# TPS630250RNCT_Buck-Boost_Switching_Regul.net
KiCad netlist of a schematic drawn in Altium Designer
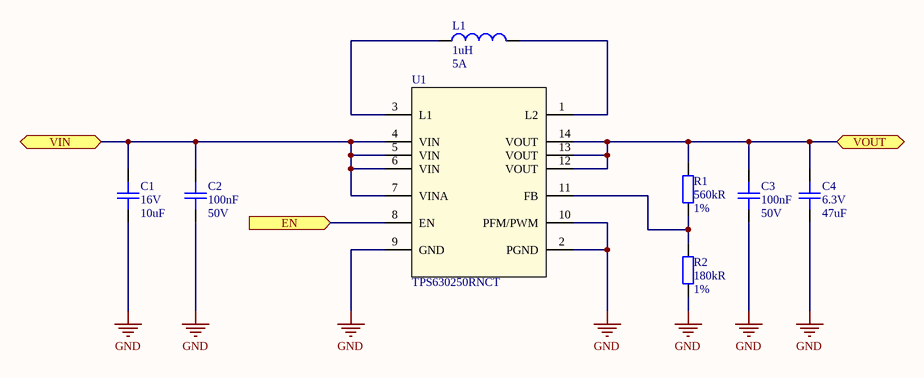
[diagram p0: TPS630250RNCT Buck-Boost Switching Regulator.SchDoc]

(export (version "E")
  (design (tool "Eeschema 10.0.6"))
  (components
    (comp (ref "C1")
      (value "CAP CER 10UF 16V X5R 0603")
      (footprint "C0603")
      (description "10µF ±10% 16V Ceramic Capacitor X5R 0603 (1608 Metric)")
      (fields
        (field (name "MANUFACTURER") "Murata")
        (field (name "MANUFACTURER PART NUMBER") "GRM188R61C106KAALJ")
        (field (name "VOLTAGE RATING") "16V")
        (field (name "CAPACITANCE") "10uF")
      )
      (libsource (lib "Control_Board_Model") (part "CAP CER 10UF 16V X5R 0603"))
    )
    (comp (ref "C2")
      (value "CAP CER 0.1UF 50V X7R 0402")
      (footprint "C0402")
      (description "0.1µF ±10% 50V Ceramic Capacitor X7R 0402 (1005 Metric)")
      (fields
        (field (name "MANUFACTURER") "TDK")
        (field (name "MANUFACTURER PART NUMBER") "CGA2B3X7R1H104K050BB")
        (field (name "CAPACITANCE") "100nF")
        (field (name "VOLTAGE") "50V")
      )
      (libsource (lib "Control_Board_Model") (part "CAP CER 0.1UF 50V X7R 0402"))
    )
    (comp (ref "C3")
      (value "CAP CER 0.1UF 50V X7R 0402")
      (footprint "C0402")
      (description "0.1µF ±10% 50V Ceramic Capacitor X7R 0402 (1005 Metric)")
      (fields
        (field (name "MANUFACTURER") "TDK")
        (field (name "MANUFACTURER PART NUMBER") "CGA2B3X7R1H104K050BB")
        (field (name "CAPACITANCE") "100nF")
        (field (name "VOLTAGE") "50V")
      )
      (libsource (lib "Control_Board_Model") (part "CAP CER 0.1UF 50V X7R 0402"))
    )
    (comp (ref "C4")
      (value "CAP CER 47UF 6.3V X5R 0603")
      (footprint "C0603")
      (description "47 µF ±20% 6.3V Ceramic Capacitor X5R 0603 (1608 Metric)")
      (fields
        (field (name "MANUFACTURER") "AVX Corporation")
        (field (name "MANUFACTURER PART NUMBER") "06036D476MAT2A")
        (field (name "VOLTAGE RATING") "6.3V")
        (field (name "CAPACITANCE") "47uF")
      )
      (libsource (lib "Control_Board_Model") (part "CAP CER 47UF 6.3V X5R 0603"))
    )
    (comp (ref "L1")
      (value "FIXED IND 1UH 5A 24 MOHM SMD")
      (footprint "IND_IHLP-1212B00")
      (description "1µH Shielded Molded Inductor 5A 24mOhm Max Nonstandard")
      (fields
        (field (name "MANUFACTURER") "Vishay Dale")
        (field (name "MANUFACTURER PART NUMBER") "IHLP1212BZER1R0M11")
        (field (name "INDUCTANCE") "1uH")
        (field (name "CURRENT RATING") "5A")
      )
      (libsource (lib "Control_Board_Model") (part "FIXED IND 1UH 5A 24 MOHM SMD"))
    )
    (comp (ref "R1")
      (value "RES SMD 560K OHM 1% 1/16W 0402")
      (footprint "R0402")
      (description "560 kOhms ±1% 0.063W, 1/16W Chip Resistor 0402 (1005 Metric) Moisture Resistant Thick Film")
      (fields
        (field (name "MANUFACTURER") "Yageo")
        (field (name "MANUFACTURER PART NUMBER") "RC0402FR-07560KL")
        (field (name "RESISTANCE") "560kR")
        (field (name "TOLERANCE") "1%")
      )
      (libsource (lib "Control_Board_Model") (part "RES SMD 560K OHM 1% 1/16W 0402"))
    )
    (comp (ref "R2")
      (value "RES SMD 180K OHM 1% 1/16W 0402")
      (footprint "R0402")
      (description "180 kOhms ±1% 0.063W, 1/16W Chip Resistor 0402 (1005 Metric) Moisture Resistant Thick Film")
      (fields
        (field (name "MANUFACTURER") "Yageo")
        (field (name "MANUFACTURER PART NUMBER") "RC0402FR-07180KL")
        (field (name "RESISTANCE") "180kR")
        (field (name "TOLERANCE") "1%")
      )
      (libsource (lib "Control_Board_Model") (part "RES SMD 180K OHM 1% 1/16W 0402"))
    )
    (comp (ref "U1")
      (value "TPS630250RNCT")
      (footprint "VFQFN-14")
      (description "Buck-Boost Switching Regulator IC Positive Adjustable 2.3V 1 Output 2A, 4A 14-VFQFN")
      (fields (field (name "MANUFACTURER") "Texas Instruments"))
      (libsource (lib "Control_Board_Model") (part "IC TPS630250RNCT REG BCK BST ADJ 2A/4A 14VQFN"))
    )
  )
  (nets
    (net (code "1") (name "/EN") (class "Default")
      (node (ref "U1") (pin "8") (pinfunction "EN_8") (pintype "passive"))
    )
    (net (code "2") (name "/VIN") (class "Default")
      (node (ref "C1") (pin "2") (pinfunction "2_2") (pintype "passive"))
      (node (ref "C2") (pin "2") (pinfunction "2_2") (pintype "passive"))
      (node (ref "U1") (pin "4") (pinfunction "VIN_4") (pintype "passive"))
      (node (ref "U1") (pin "5") (pinfunction "VIN_5") (pintype "passive"))
      (node (ref "U1") (pin "6") (pinfunction "VIN_6") (pintype "passive"))
      (node (ref "U1") (pin "7") (pinfunction "VINA_7") (pintype "passive"))
    )
    (net (code "3") (name "/VOUT") (class "Default")
      (node (ref "C3") (pin "2") (pinfunction "2_2") (pintype "passive"))
      (node (ref "C4") (pin "2") (pinfunction "2_2") (pintype "passive"))
      (node (ref "R1") (pin "2") (pinfunction "2_2") (pintype "passive"))
      (node (ref "U1") (pin "12") (pinfunction "VOUT_12") (pintype "passive"))
      (node (ref "U1") (pin "13") (pinfunction "VOUT_13") (pintype "passive"))
      (node (ref "U1") (pin "14") (pinfunction "VOUT_14") (pintype "passive"))
    )
    (net (code "4") (name "GND") (class "Default")
      (node (ref "C1") (pin "1") (pinfunction "1_1") (pintype "passive"))
      (node (ref "C2") (pin "1") (pinfunction "1_1") (pintype "passive"))
      (node (ref "C3") (pin "1") (pinfunction "1_1") (pintype "passive"))
      (node (ref "C4") (pin "1") (pinfunction "1_1") (pintype "passive"))
      (node (ref "R2") (pin "1") (pinfunction "1_1") (pintype "passive"))
      (node (ref "U1") (pin "10") (pinfunction "PFM/PWM_10") (pintype "passive"))
      (node (ref "U1") (pin "2") (pinfunction "PGND_2") (pintype "passive"))
      (node (ref "U1") (pin "9") (pinfunction "GND_9") (pintype "passive"))
    )
    (net (code "5") (name "Net-(U1-FB)") (class "Default")
      (node (ref "R1") (pin "1") (pinfunction "1_1") (pintype "passive"))
      (node (ref "R2") (pin "2") (pinfunction "2_2") (pintype "passive"))
      (node (ref "U1") (pin "11") (pinfunction "FB_11") (pintype "passive"))
    )
    (net (code "6") (name "Net-(U1-L1)") (class "Default")
      (node (ref "L1") (pin "1") (pinfunction "1_1") (pintype "passive"))
      (node (ref "U1") (pin "3") (pinfunction "L1_3") (pintype "passive"))
    )
    (net (code "7") (name "Net-(U1-L2)") (class "Default")
      (node (ref "L1") (pin "2") (pinfunction "2_2") (pintype "passive"))
      (node (ref "U1") (pin "1") (pinfunction "L2_1") (pintype "passive"))
    )
  )
)
